# Port_Power.net
KiCad netlist of a schematic drawn in Altium Designer
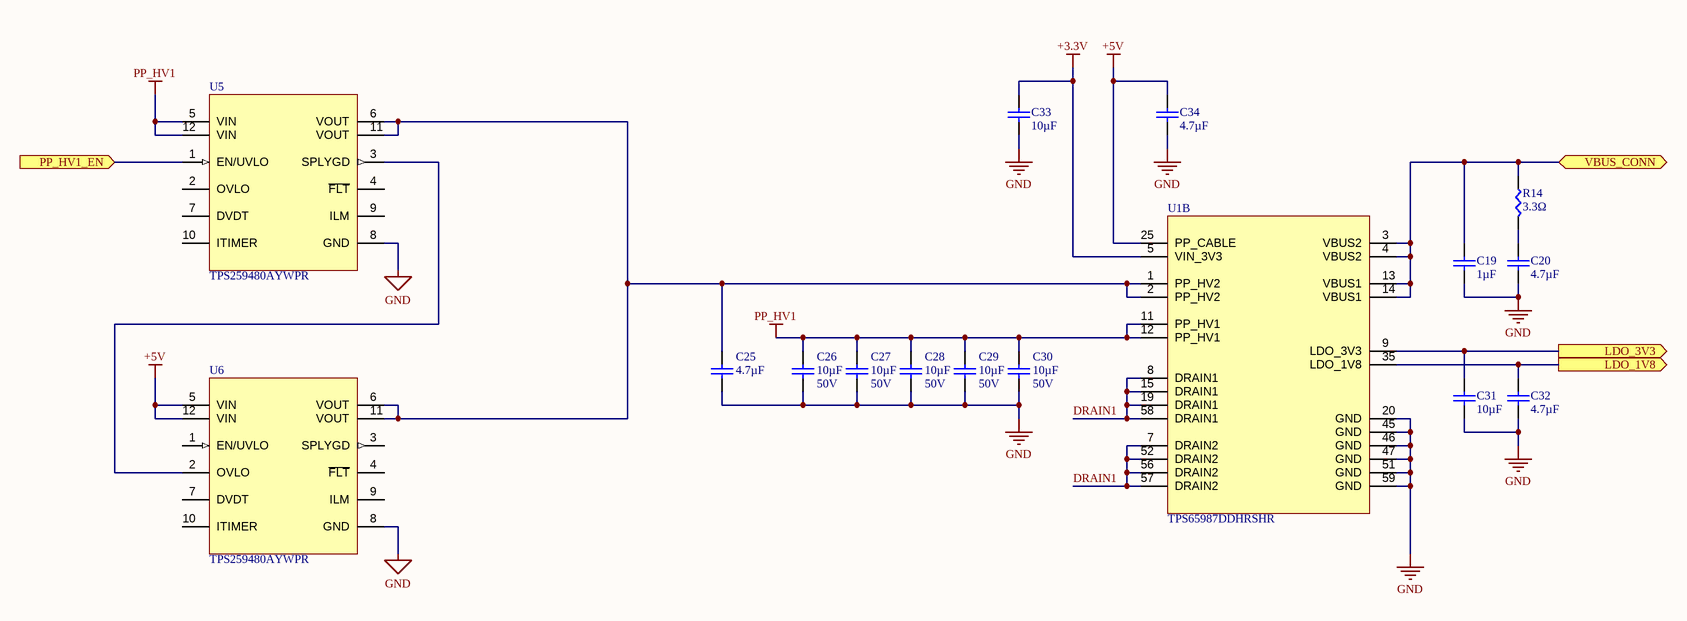
[diagram p0: Port_Power.SchDoc]

(export (version "E")
  (design (tool "Eeschema 10.0.6"))
  (components
    (comp (ref "C19")
      (value "1µF")
      (footprint "CAP0402")
      (description "1 µF ±10% 50V Ceramic Capacitor X5R 0402 (1005 Metric)")
      (fields (field (name "VOLTAGE") "50V") (field (name "Comment") "GRM155R61H105KE05D"))
      (libsource (lib "Schlib1") (part "GRM155R61H105KE05D"))
    )
    (comp (ref "C20")
      (value "4.7µF")
      (footprint "CAP0805")
      (description "4.7 µF ±10% 50V Ceramic Capacitor X5R 0805 (2012 Metric)")
      (fields (field (name "VOLTAGE") "50V") (field (name "Comment") "GRT21BR61H475KE13L"))
      (libsource (lib "Schlib1") (part "GRT21BR61H475KE13L"))
    )
    (comp (ref "C25")
      (value "4.7µF")
      (footprint "CAP0805")
      (description "4.7 µF ±10% 50V Ceramic Capacitor X5R 0805 (2012 Metric)")
      (fields (field (name "VOLTAGE") "50V") (field (name "Comment") "GRT21BR61H475KE13L"))
      (libsource (lib "Schlib1") (part "GRT21BR61H475KE13L"))
    )
    (comp (ref "C26")
      (value "10µF")
      (footprint "CAP1206")
      (description "10 µF ±10% 50V Ceramic Capacitor X5R 1206 (3216 Metric)")
      (fields (field (name "VOLTAGE") "50V") (field (name "Comment") "CL31A106KBHNNNE"))
      (libsource (lib "Schlib1") (part "CL31A106KBHNNNE"))
    )
    (comp (ref "C27")
      (value "10µF")
      (footprint "CAP1206")
      (description "10 µF ±10% 50V Ceramic Capacitor X5R 1206 (3216 Metric)")
      (fields (field (name "VOLTAGE") "50V") (field (name "Comment") "CL31A106KBHNNNE"))
      (libsource (lib "Schlib1") (part "CL31A106KBHNNNE"))
    )
    (comp (ref "C28")
      (value "10µF")
      (footprint "CAP1206")
      (description "10 µF ±10% 50V Ceramic Capacitor X5R 1206 (3216 Metric)")
      (fields (field (name "VOLTAGE") "50V") (field (name "Comment") "CL31A106KBHNNNE"))
      (libsource (lib "Schlib1") (part "CL31A106KBHNNNE"))
    )
    (comp (ref "C29")
      (value "10µF")
      (footprint "CAP1206")
      (description "10 µF ±10% 50V Ceramic Capacitor X5R 1206 (3216 Metric)")
      (fields (field (name "VOLTAGE") "50V") (field (name "Comment") "CL31A106KBHNNNE"))
      (libsource (lib "Schlib1") (part "CL31A106KBHNNNE"))
    )
    (comp (ref "C30")
      (value "10µF")
      (footprint "CAP1206")
      (description "10 µF ±10% 50V Ceramic Capacitor X5R 1206 (3216 Metric)")
      (fields (field (name "VOLTAGE") "50V") (field (name "Comment") "CL31A106KBHNNNE"))
      (libsource (lib "Schlib1") (part "CL31A106KBHNNNE"))
    )
    (comp (ref "C31")
      (value "10µF")
      (footprint "CAP0402")
      (description "10 µF ±20% 6.3V Ceramic Capacitor X5R 0402 (1005 Metric)")
      (fields (field (name "VOLTAGE") "6.3V") (field (name "Comment") "CL05A106MQ5NUNC"))
      (libsource (lib "Schlib1") (part "CL05A106MQ5NUNC"))
    )
    (comp (ref "C32")
      (value "4.7µF")
      (footprint "CAP0805")
      (description "4.7 µF ±10% 50V Ceramic Capacitor X5R 0805 (2012 Metric)")
      (fields (field (name "VOLTAGE") "50V") (field (name "Comment") "GRT21BR61H475KE13L"))
      (libsource (lib "Schlib1") (part "GRT21BR61H475KE13L"))
    )
    (comp (ref "C33")
      (value "10µF")
      (footprint "CAP0402")
      (description "10 µF ±20% 6.3V Ceramic Capacitor X5R 0402 (1005 Metric)")
      (fields (field (name "VOLTAGE") "6.3V") (field (name "Comment") "CL05A106MQ5NUNC"))
      (libsource (lib "Schlib1") (part "CL05A106MQ5NUNC"))
    )
    (comp (ref "C34")
      (value "4.7µF")
      (footprint "CAP0805")
      (description "4.7 µF ±10% 50V Ceramic Capacitor X5R 0805 (2012 Metric)")
      (fields (field (name "VOLTAGE") "50V") (field (name "Comment") "GRT21BR61H475KE13L"))
      (libsource (lib "Schlib1") (part "GRT21BR61H475KE13L"))
    )
    (comp (ref "R14")
      (value "3.3Ω")
      (footprint "RES0402")
      (fields (field (name "Comment") "ESR10EZPJ3R3"))
      (libsource (lib "Schlib1") (part "ESR10EZPJ3R3"))
    )
    (comp (ref "U1")
      (value "TPS65987DDHRSHR")
      (footprint "56-VQFN (7x7)")
      (description "USB, Type-C Controller PMIC 56-VQFN (7x7)")
      (fields (field (name "MANUFACTURER") "Texas Instruments"))
      (libsource (lib "Schlib1") (part "TPS65987DDHRSHR"))
    )
    (comp (ref "U5")
      (value "TPS259480AYWPR")
      (description "Electronic Fuse Regulator High-Side 8A 12-DSBGA (2.43x1.74)")
      (fields (field (name "MANUFACTURER") "Texas Instruments"))
      (libsource (lib "Schlib1") (part "TPS259480AYWPR"))
    )
    (comp (ref "U6")
      (value "TPS259480AYWPR")
      (description "Electronic Fuse Regulator High-Side 8A 12-DSBGA (2.43x1.74)")
      (fields (field (name "MANUFACTURER") "Texas Instruments"))
      (libsource (lib "Schlib1") (part "TPS259480AYWPR"))
    )
  )
  (nets
    (net (code "1") (name "+3.3V") (class "Default")
      (node (ref "C33") (pin "2") (pinfunction "2_2") (pintype "passive"))
      (node (ref "U1") (pin "5") (pinfunction "VIN_3V3_5") (pintype "passive"))
    )
    (net (code "2") (name "+5V") (class "Default")
      (node (ref "C34") (pin "2") (pinfunction "2_2") (pintype "passive"))
      (node (ref "U1") (pin "25") (pinfunction "PP_CABLE_25") (pintype "passive"))
      (node (ref "U6") (pin "12") (pinfunction "VIN_12") (pintype "passive"))
      (node (ref "U6") (pin "5") (pinfunction "VIN_5") (pintype "passive"))
    )
    (net (code "3") (name "/DRAIN1") (class "Default")
      (node (ref "U1") (pin "15") (pinfunction "DRAIN1_15") (pintype "passive"))
      (node (ref "U1") (pin "19") (pinfunction "DRAIN1_19") (pintype "passive"))
      (node (ref "U1") (pin "52") (pinfunction "DRAIN2_52") (pintype "passive"))
      (node (ref "U1") (pin "56") (pinfunction "DRAIN2_56") (pintype "passive"))
      (node (ref "U1") (pin "57") (pinfunction "DRAIN2_57") (pintype "passive"))
      (node (ref "U1") (pin "58") (pinfunction "DRAIN1_58") (pintype "passive"))
      (node (ref "U1") (pin "7") (pinfunction "DRAIN2_7") (pintype "passive"))
      (node (ref "U1") (pin "8") (pinfunction "DRAIN1_8") (pintype "passive"))
    )
    (net (code "4") (name "/LDO_1V8") (class "Default")
      (node (ref "C32") (pin "2") (pinfunction "2_2") (pintype "passive"))
      (node (ref "U1") (pin "35") (pinfunction "LDO_1V8_35") (pintype "passive"))
    )
    (net (code "5") (name "/LDO_3V3") (class "Default")
      (node (ref "C31") (pin "2") (pinfunction "2_2") (pintype "passive"))
      (node (ref "U1") (pin "9") (pinfunction "LDO_3V3_9") (pintype "passive"))
    )
    (net (code "6") (name "/PP_HV1_EN") (class "Default")
      (node (ref "U5") (pin "1") (pinfunction "EN/UVLO_1") (pintype "input"))
    )
    (net (code "7") (name "/VBUS_CONN") (class "Default")
      (node (ref "C19") (pin "2") (pinfunction "2_2") (pintype "passive"))
      (node (ref "R14") (pin "2") (pinfunction "2_2") (pintype "passive"))
      (node (ref "U1") (pin "13") (pinfunction "VBUS1_13") (pintype "passive"))
      (node (ref "U1") (pin "14") (pinfunction "VBUS1_14") (pintype "passive"))
      (node (ref "U1") (pin "3") (pinfunction "VBUS2_3") (pintype "passive"))
      (node (ref "U1") (pin "4") (pinfunction "VBUS2_4") (pintype "passive"))
    )
    (net (code "8") (name "GND") (class "Default")
      (node (ref "C19") (pin "1") (pinfunction "1_1") (pintype "passive"))
      (node (ref "C20") (pin "1") (pinfunction "1_1") (pintype "passive"))
      (node (ref "C25") (pin "2") (pinfunction "2_2") (pintype "passive"))
      (node (ref "C26") (pin "1") (pinfunction "1_1") (pintype "passive"))
      (node (ref "C27") (pin "1") (pinfunction "1_1") (pintype "passive"))
      (node (ref "C28") (pin "1") (pinfunction "1_1") (pintype "passive"))
      (node (ref "C29") (pin "1") (pinfunction "1_1") (pintype "passive"))
      (node (ref "C30") (pin "1") (pinfunction "1_1") (pintype "passive"))
      (node (ref "C31") (pin "1") (pinfunction "1_1") (pintype "passive"))
      (node (ref "C32") (pin "1") (pinfunction "1_1") (pintype "passive"))
      (node (ref "C33") (pin "1") (pinfunction "1_1") (pintype "passive"))
      (node (ref "C34") (pin "1") (pinfunction "1_1") (pintype "passive"))
      (node (ref "U1") (pin "20") (pinfunction "GND_20") (pintype "passive"))
      (node (ref "U1") (pin "45") (pinfunction "GND_45") (pintype "passive"))
      (node (ref "U1") (pin "46") (pinfunction "GND_46") (pintype "passive"))
      (node (ref "U1") (pin "47") (pinfunction "GND_47") (pintype "passive"))
      (node (ref "U1") (pin "51") (pinfunction "GND_51") (pintype "passive"))
      (node (ref "U1") (pin "59") (pinfunction "GND_59") (pintype "passive"))
      (node (ref "U5") (pin "8") (pinfunction "GND_8") (pintype "passive"))
      (node (ref "U6") (pin "8") (pinfunction "GND_8") (pintype "passive"))
    )
    (net (code "9") (name "Net-(C20-Pad2)") (class "Default")
      (node (ref "C20") (pin "2") (pinfunction "2_2") (pintype "passive"))
      (node (ref "R14") (pin "1") (pinfunction "1_1") (pintype "passive"))
    )
    (net (code "10") (name "Net-(C25-Pad1)") (class "Default")
      (node (ref "C25") (pin "1") (pinfunction "1_1") (pintype "passive"))
      (node (ref "U1") (pin "1") (pinfunction "PP_HV2_1") (pintype "passive"))
      (node (ref "U1") (pin "2") (pinfunction "PP_HV2_2") (pintype "passive"))
      (node (ref "U5") (pin "11") (pinfunction "VOUT_11") (pintype "passive"))
      (node (ref "U5") (pin "6") (pinfunction "VOUT_6") (pintype "passive"))
      (node (ref "U6") (pin "11") (pinfunction "VOUT_11") (pintype "passive"))
      (node (ref "U6") (pin "6") (pinfunction "VOUT_6") (pintype "passive"))
    )
    (net (code "11") (name "Net-(U5-SPLYGD)") (class "Default")
      (node (ref "U5") (pin "3") (pinfunction "SPLYGD_3") (pintype "output"))
      (node (ref "U6") (pin "2") (pinfunction "OVLO_2") (pintype "passive"))
    )
    (net (code "12") (name "PP_HV1") (class "Default")
      (node (ref "C26") (pin "2") (pinfunction "2_2") (pintype "passive"))
      (node (ref "C27") (pin "2") (pinfunction "2_2") (pintype "passive"))
      (node (ref "C28") (pin "2") (pinfunction "2_2") (pintype "passive"))
      (node (ref "C29") (pin "2") (pinfunction "2_2") (pintype "passive"))
      (node (ref "C30") (pin "2") (pinfunction "2_2") (pintype "passive"))
      (node (ref "U1") (pin "11") (pinfunction "PP_HV1_11") (pintype "passive"))
      (node (ref "U1") (pin "12") (pinfunction "PP_HV1_12") (pintype "passive"))
      (node (ref "U5") (pin "12") (pinfunction "VIN_12") (pintype "passive"))
      (node (ref "U5") (pin "5") (pinfunction "VIN_5") (pintype "passive"))
    )
    (net (code "13") (name "unconnected-(U5-DVDT-Pad7)") (class "Default")
      (node (ref "U5") (pin "7") (pinfunction "DVDT_7") (pintype "passive"))
    )
    (net (code "14") (name "unconnected-(U5-ILM-Pad9)") (class "Default")
      (node (ref "U5") (pin "9") (pinfunction "ILM_9") (pintype "passive"))
    )
    (net (code "15") (name "unconnected-(U5-ITIMER-Pad10)") (class "Default")
      (node (ref "U5") (pin "10") (pinfunction "ITIMER_10") (pintype "passive"))
    )
    (net (code "16") (name "unconnected-(U5-OVLO-Pad2)") (class "Default")
      (node (ref "U5") (pin "2") (pinfunction "OVLO_2") (pintype "passive"))
    )
    (net (code "17") (name "unconnected-(U5-~{FLT}-Pad4)") (class "Default")
      (node (ref "U5") (pin "4") (pinfunction "~{FLT}_4") (pintype "passive"))
    )
    (net (code "18") (name "unconnected-(U6-DVDT-Pad7)") (class "Default")
      (node (ref "U6") (pin "7") (pinfunction "DVDT_7") (pintype "passive"))
    )
    (net (code "19") (name "unconnected-(U6-EN{slash}UVLO-Pad1)") (class "Default")
      (node (ref "U6") (pin "1") (pinfunction "EN/UVLO_1") (pintype "input"))
    )
    (net (code "20") (name "unconnected-(U6-ILM-Pad9)") (class "Default")
      (node (ref "U6") (pin "9") (pinfunction "ILM_9") (pintype "passive"))
    )
    (net (code "21") (name "unconnected-(U6-ITIMER-Pad10)") (class "Default")
      (node (ref "U6") (pin "10") (pinfunction "ITIMER_10") (pintype "passive"))
    )
    (net (code "22") (name "unconnected-(U6-SPLYGD-Pad3)") (class "Default")
      (node (ref "U6") (pin "3") (pinfunction "SPLYGD_3") (pintype "output"))
    )
    (net (code "23") (name "unconnected-(U6-~{FLT}-Pad4)") (class "Default")
      (node (ref "U6") (pin "4") (pinfunction "~{FLT}_4") (pintype "passive"))
    )
  )
)
